# resistor-voltage-divider.net
KiCad netlist of a schematic drawn in EAGLE
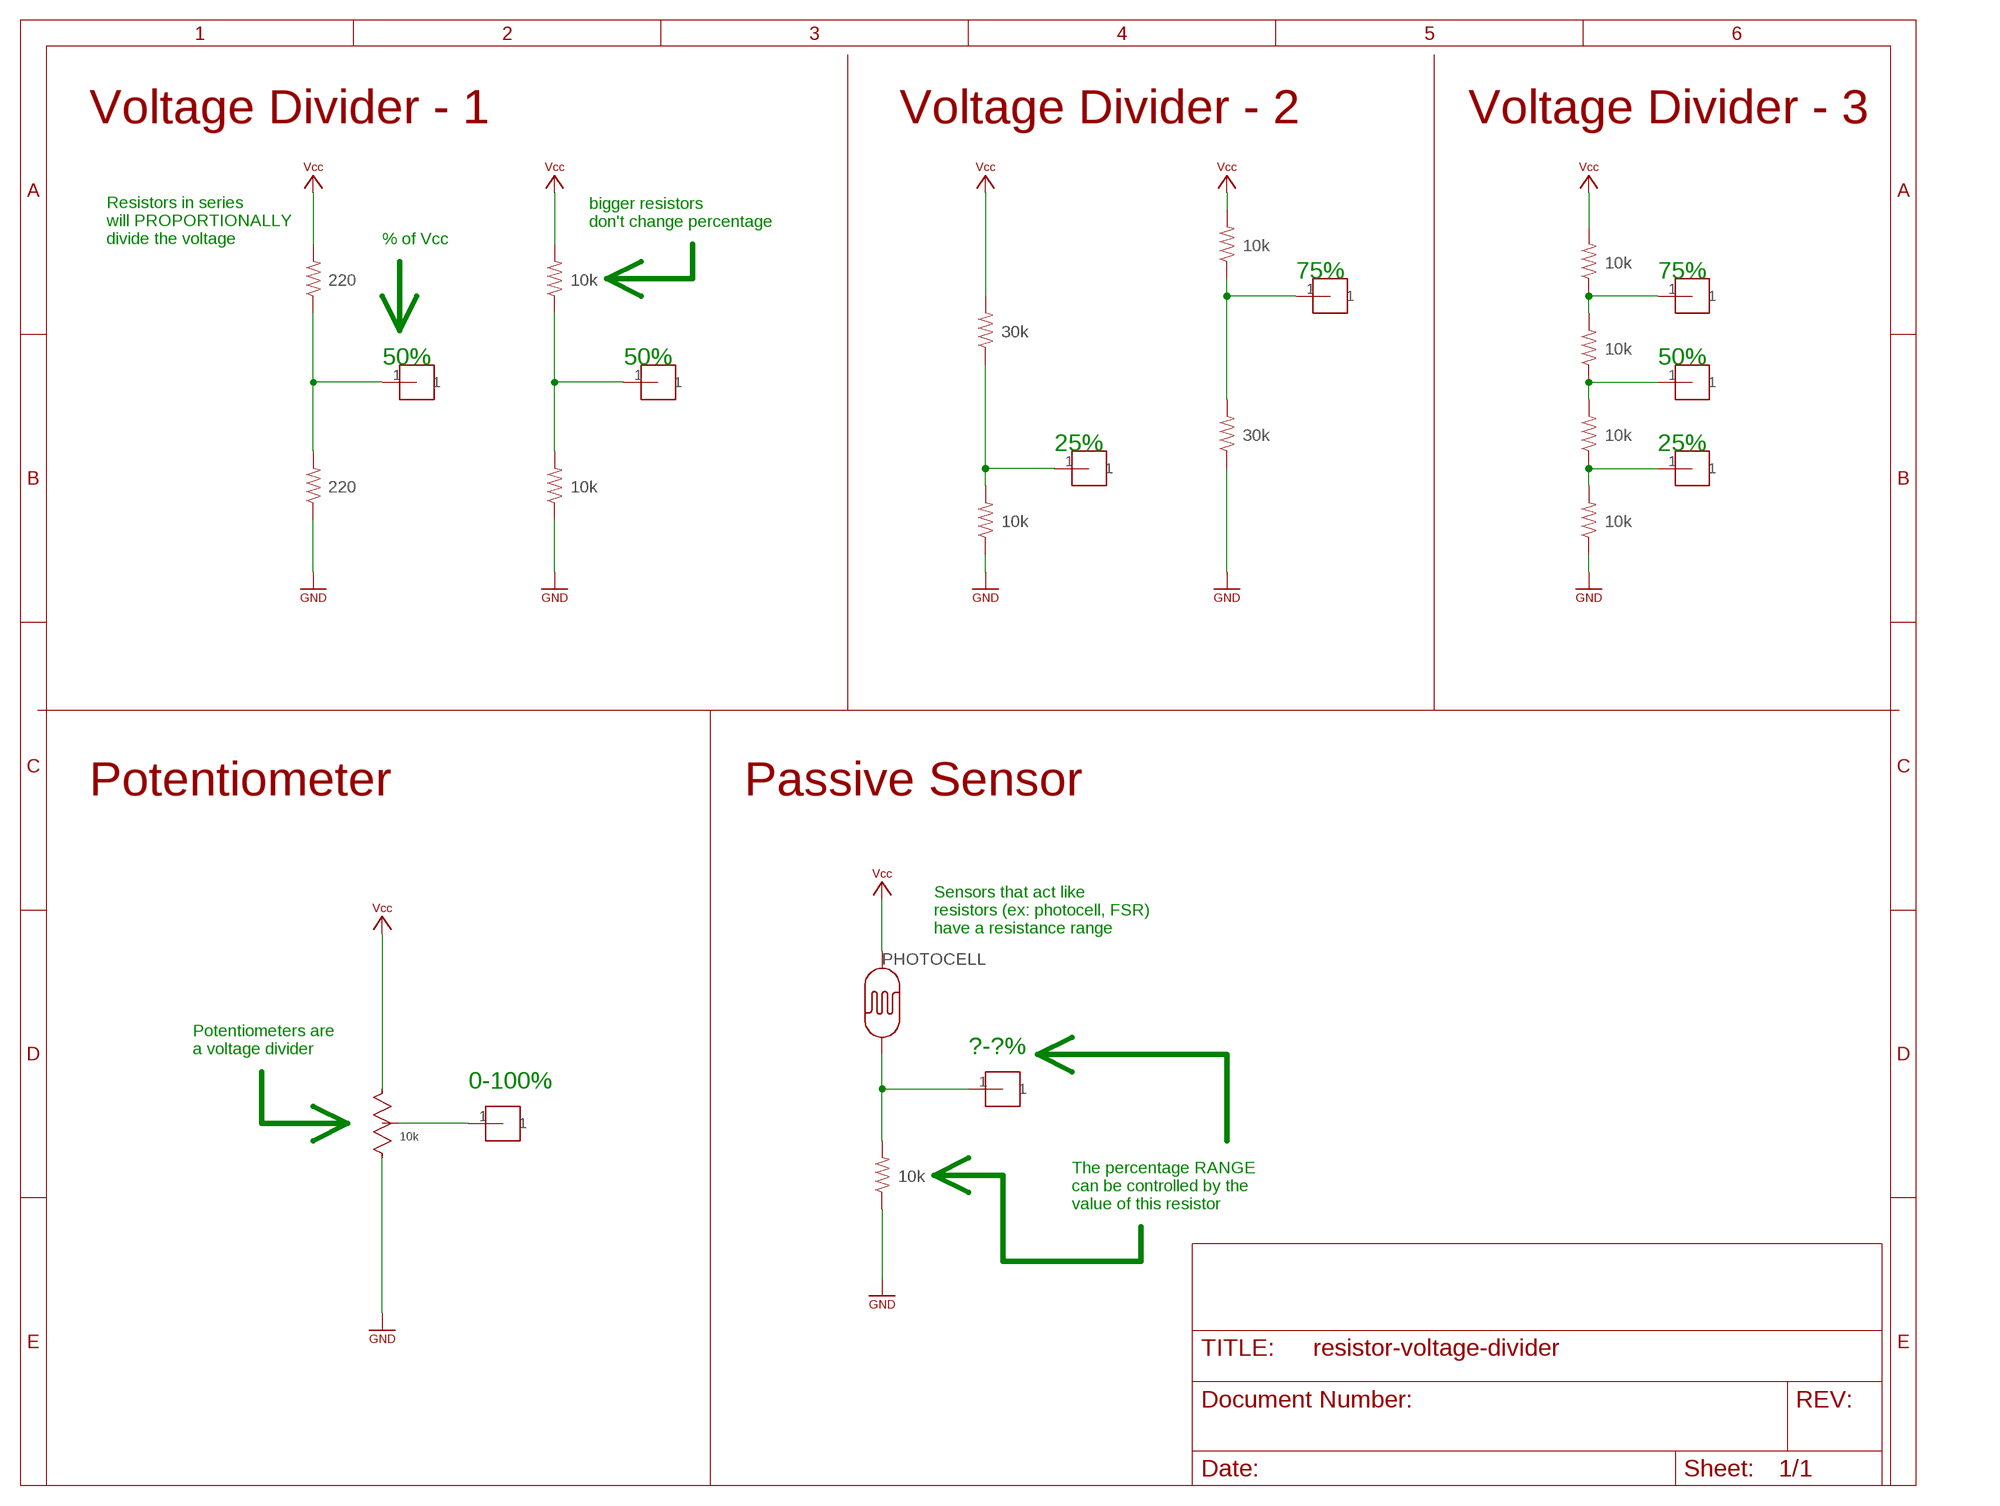
[diagram p0: schematic, sheet 1]

(export (version "E")
  (design (tool "Eeschema 10.0.6"))
  (components
    (comp (ref "PHOTOCELL")
      (value "PHOTOCELLPTH")
      (footprint "eagle-import:PHOTOCELL")
      (libsource (lib "eagle-import") (part "PHOTOCELLPTH"))
    )
    (comp (ref "R13")
      (value "220")
      (footprint "eagle-import:0805")
      (libsource (lib "eagle-import") (part "COMPONENT_RESISTOR-0805"))
    )
    (comp (ref "R15")
      (value "220")
      (footprint "eagle-import:0805")
      (libsource (lib "eagle-import") (part "COMPONENT_RESISTOR-0805"))
    )
    (comp (ref "R16")
      (value "10k")
      (footprint "eagle-import:0805")
      (libsource (lib "eagle-import") (part "COMPONENT_RESISTOR-0805"))
    )
    (comp (ref "R17")
      (value "10k")
      (footprint "eagle-import:0805")
      (libsource (lib "eagle-import") (part "COMPONENT_RESISTOR-0805"))
    )
    (comp (ref "R18")
      (value "10k")
      (footprint "eagle-import:0805")
      (libsource (lib "eagle-import") (part "COMPONENT_RESISTOR-0805"))
    )
    (comp (ref "R19")
      (value "30k")
      (footprint "eagle-import:0805")
      (libsource (lib "eagle-import") (part "COMPONENT_RESISTOR-0805"))
    )
    (comp (ref "R20")
      (value "30k")
      (footprint "eagle-import:0805")
      (libsource (lib "eagle-import") (part "COMPONENT_RESISTOR-0805"))
    )
    (comp (ref "R21")
      (value "10k")
      (footprint "eagle-import:0805")
      (libsource (lib "eagle-import") (part "COMPONENT_RESISTOR-0805"))
    )
    (comp (ref "R22")
      (value "10k")
      (footprint "eagle-import:0805")
      (libsource (lib "eagle-import") (part "COMPONENT_RESISTOR-0805"))
    )
    (comp (ref "R23")
      (value "10k")
      (footprint "eagle-import:0805")
      (libsource (lib "eagle-import") (part "COMPONENT_RESISTOR-0805"))
    )
    (comp (ref "R24")
      (value "10k")
      (footprint "eagle-import:0805")
      (libsource (lib "eagle-import") (part "COMPONENT_RESISTOR-0805"))
    )
    (comp (ref "R25")
      (value "10k")
      (footprint "eagle-import:0805")
      (libsource (lib "eagle-import") (part "COMPONENT_RESISTOR-0805"))
    )
    (comp (ref "R26")
      (value "10k")
      (footprint "eagle-import:0805")
      (libsource (lib "eagle-import") (part "COMPONENT_RESISTOR-0805"))
    )
    (comp (ref "U$1")
      (value "HEADER-1-TESTPOINT")
      (footprint "eagle-import:TESTPOINT-1")
      (libsource (lib "eagle-import") (part "HEADER-1-TESTPOINT"))
    )
    (comp (ref "U$2")
      (value "HEADER-1-TESTPOINT")
      (footprint "eagle-import:TESTPOINT-1")
      (libsource (lib "eagle-import") (part "HEADER-1-TESTPOINT"))
    )
    (comp (ref "U$3")
      (value "HEADER-1-TESTPOINT")
      (footprint "eagle-import:TESTPOINT-1")
      (libsource (lib "eagle-import") (part "HEADER-1-TESTPOINT"))
    )
    (comp (ref "U$4")
      (value "HEADER-1-TESTPOINT")
      (footprint "eagle-import:TESTPOINT-1")
      (libsource (lib "eagle-import") (part "HEADER-1-TESTPOINT"))
    )
    (comp (ref "U$5")
      (value "HEADER-1-TESTPOINT")
      (footprint "eagle-import:TESTPOINT-1")
      (libsource (lib "eagle-import") (part "HEADER-1-TESTPOINT"))
    )
    (comp (ref "U$6")
      (value "HEADER-1-TESTPOINT")
      (footprint "eagle-import:TESTPOINT-1")
      (libsource (lib "eagle-import") (part "HEADER-1-TESTPOINT"))
    )
    (comp (ref "U$7")
      (value "HEADER-1-TESTPOINT")
      (footprint "eagle-import:TESTPOINT-1")
      (libsource (lib "eagle-import") (part "HEADER-1-TESTPOINT"))
    )
    (comp (ref "U$8")
      (value "HEADER-1-TESTPOINT")
      (footprint "eagle-import:TESTPOINT-1")
      (libsource (lib "eagle-import") (part "HEADER-1-TESTPOINT"))
    )
    (comp (ref "U$9")
      (value "HEADER-1-TESTPOINT")
      (footprint "eagle-import:TESTPOINT-1")
      (libsource (lib "eagle-import") (part "HEADER-1-TESTPOINT"))
    )
    (comp (ref "U$10")
      (value "10k")
      (footprint "eagle-import:TC33X-2-103E")
      (libsource (lib "eagle-import") (part "COMPONENT_POTENTIOMETER"))
    )
  )
  (nets
    (net (code "2") (name "Net-(PHOTOCELL-P$1)") (class "Default")
      (node (ref "PHOTOCELL") (pin "1") (pinfunction "P$1_1") (pintype "bidirectional"))
      (node (ref "R26") (pin "2") (pinfunction "2_2") (pintype "passive"))
      (node (ref "U$8") (pin "1") (pinfunction "1_1") (pintype "bidirectional"))
    )
    (net (code "3") (name "Net-(R13-Pad2)") (class "Default")
      (node (ref "R13") (pin "2") (pinfunction "2_2") (pintype "passive"))
      (node (ref "R15") (pin "1") (pinfunction "1_1") (pintype "passive"))
      (node (ref "U$1") (pin "1") (pinfunction "1_1") (pintype "bidirectional"))
    )
    (net (code "4") (name "Net-(R16-Pad1)") (class "Default")
      (node (ref "R16") (pin "1") (pinfunction "1_1") (pintype "passive"))
      (node (ref "R17") (pin "2") (pinfunction "2_2") (pintype "passive"))
      (node (ref "U$2") (pin "1") (pinfunction "1_1") (pintype "bidirectional"))
    )
    (net (code "5") (name "Net-(R18-Pad2)") (class "Default")
      (node (ref "R18") (pin "2") (pinfunction "2_2") (pintype "passive"))
      (node (ref "R19") (pin "1") (pinfunction "1_1") (pintype "passive"))
      (node (ref "U$3") (pin "1") (pinfunction "1_1") (pintype "bidirectional"))
    )
    (net (code "6") (name "Net-(R20-Pad2)") (class "Default")
      (node (ref "R20") (pin "2") (pinfunction "2_2") (pintype "passive"))
      (node (ref "R21") (pin "1") (pinfunction "1_1") (pintype "passive"))
      (node (ref "U$4") (pin "1") (pinfunction "1_1") (pintype "bidirectional"))
    )
    (net (code "7") (name "Net-(R22-Pad1)") (class "Default")
      (node (ref "R22") (pin "1") (pinfunction "1_1") (pintype "passive"))
      (node (ref "R23") (pin "2") (pinfunction "2_2") (pintype "passive"))
      (node (ref "U$5") (pin "1") (pinfunction "1_1") (pintype "bidirectional"))
    )
    (net (code "8") (name "Net-(R23-Pad1)") (class "Default")
      (node (ref "R23") (pin "1") (pinfunction "1_1") (pintype "passive"))
      (node (ref "R24") (pin "2") (pinfunction "2_2") (pintype "passive"))
      (node (ref "U$6") (pin "1") (pinfunction "1_1") (pintype "bidirectional"))
    )
    (net (code "9") (name "Net-(R24-Pad1)") (class "Default")
      (node (ref "R24") (pin "1") (pinfunction "1_1") (pintype "passive"))
      (node (ref "R25") (pin "2") (pinfunction "2_2") (pintype "passive"))
      (node (ref "U$7") (pin "1") (pinfunction "1_1") (pintype "bidirectional"))
    )
    (net (code "10") (name "Net-(U$10-WIPER)") (class "Default")
      (node (ref "U$10") (pin "2") (pinfunction "WIPER_2") (pintype "bidirectional"))
      (node (ref "U$9") (pin "1") (pinfunction "1_1") (pintype "bidirectional"))
    )
    (net (code "11") (name "SYMBOL_GND") (class "Default")
      (node (ref "R13") (pin "1") (pinfunction "1_1") (pintype "passive"))
      (node (ref "R17") (pin "1") (pinfunction "1_1") (pintype "passive"))
      (node (ref "R18") (pin "1") (pinfunction "1_1") (pintype "passive"))
      (node (ref "R20") (pin "1") (pinfunction "1_1") (pintype "passive"))
      (node (ref "R25") (pin "1") (pinfunction "1_1") (pintype "passive"))
      (node (ref "R26") (pin "1") (pinfunction "1_1") (pintype "passive"))
      (node (ref "U$10") (pin "3") (pinfunction "B_3") (pintype "bidirectional"))
    )
    (net (code "12") (name "SYMBOL_VCC") (class "Default")
      (node (ref "PHOTOCELL") (pin "2") (pinfunction "P$2_2") (pintype "bidirectional"))
      (node (ref "R15") (pin "2") (pinfunction "2_2") (pintype "passive"))
      (node (ref "R16") (pin "2") (pinfunction "2_2") (pintype "passive"))
      (node (ref "R19") (pin "2") (pinfunction "2_2") (pintype "passive"))
      (node (ref "R21") (pin "2") (pinfunction "2_2") (pintype "passive"))
      (node (ref "R22") (pin "2") (pinfunction "2_2") (pintype "passive"))
      (node (ref "U$10") (pin "1") (pinfunction "A_1") (pintype "bidirectional"))
    )
  )
)
